# 7-PWM_INTERLOCK.net
KiCad netlist of a schematic drawn in Altium Designer
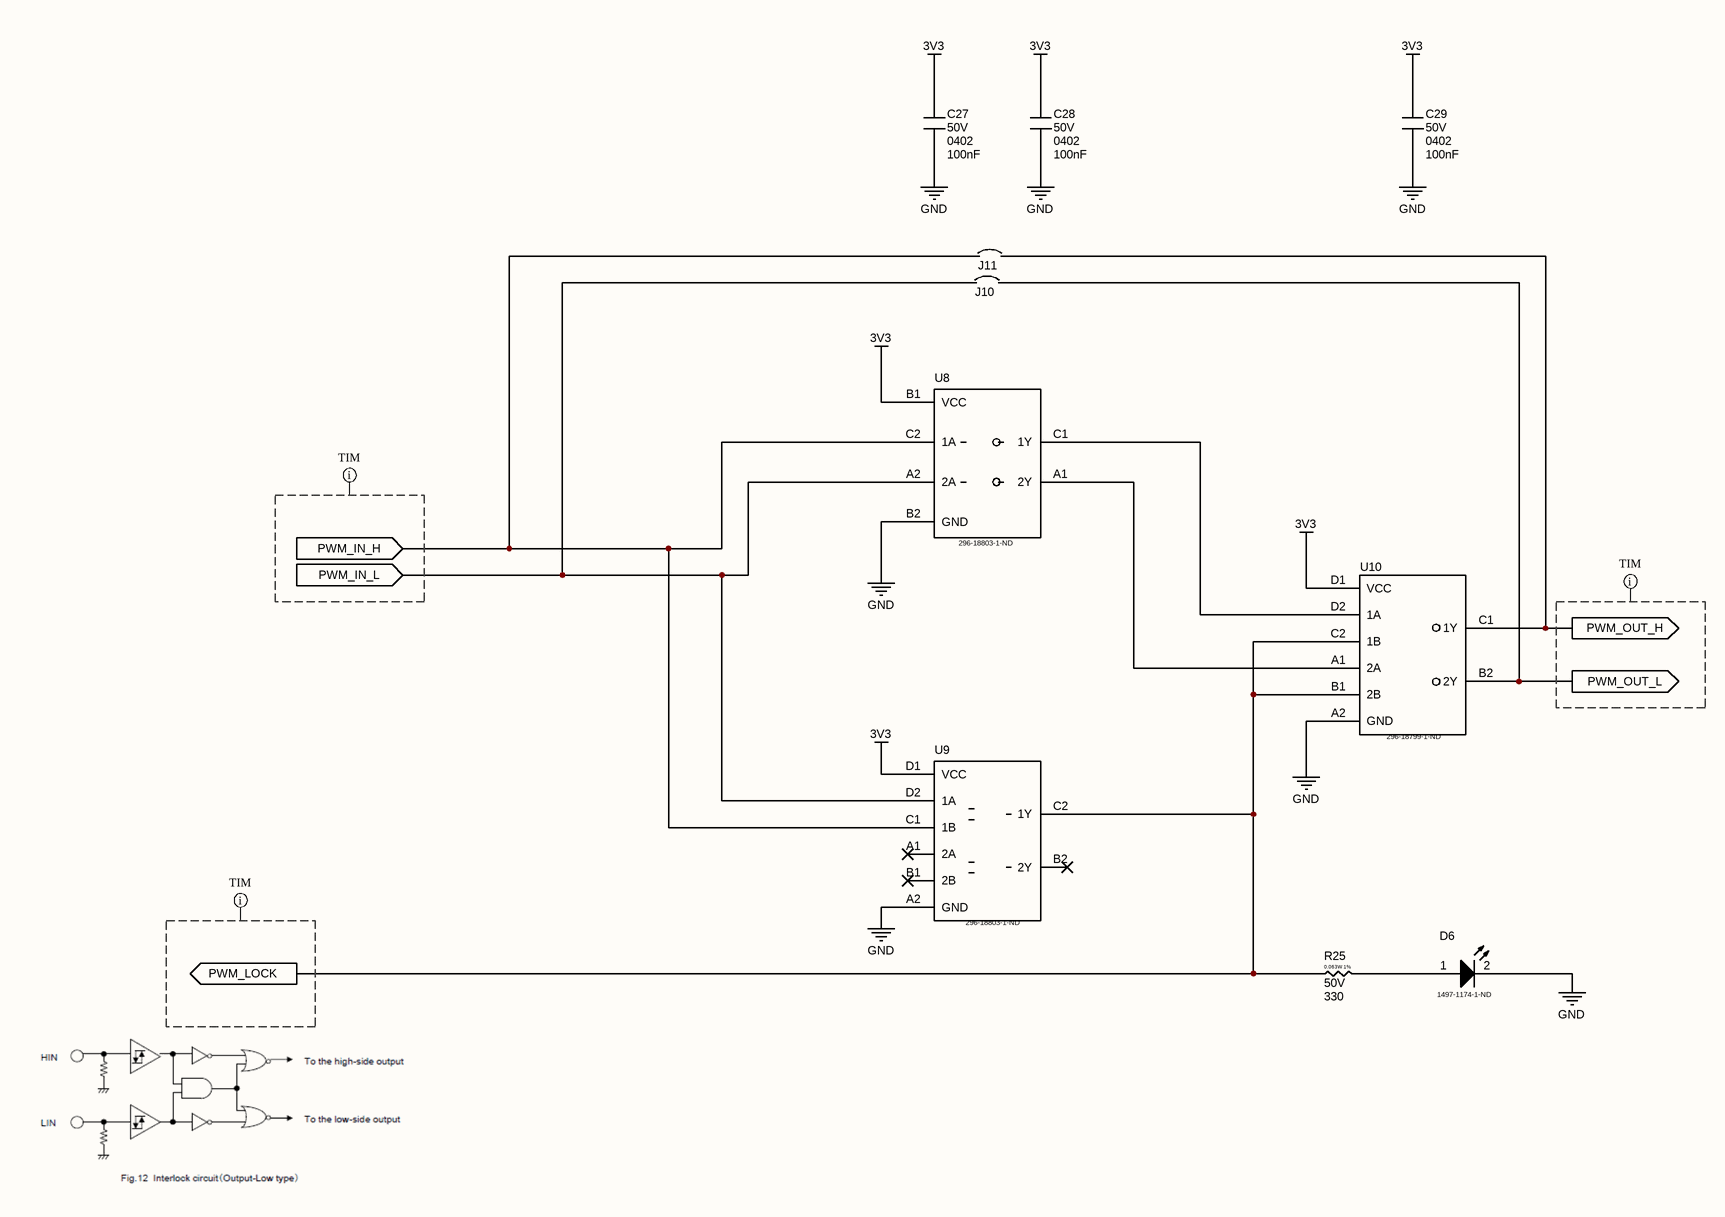
[diagram p0: 7-PWM_INTERLOCK.SchDoc]

(export (version "E")
  (design (tool "Eeschema 10.0.6"))
  (components
    (comp (ref "C27")
      (value "100nF")
      (footprint "C 0402(1005)x0.5")
      (description "SMD-0402 100nF 50V X7R 10%")
      (fields
        (field (name "PART NUMBER") "CL05B104KB5NNNC")
        (field (name "MANUFACTURER") "Samsung")
        (field (name "VDC") "50V")
        (field (name "PACKAGE") "0402")
        (field (name "PUBLISHER") "Hefest")
      )
      (libsource (lib "LIB_PASSIVE") (part "CAP 0402 100nF 50V X7R"))
    )
    (comp (ref "C28")
      (value "100nF")
      (footprint "C 0402(1005)x0.5")
      (description "SMD-0402 100nF 50V X7R 10%")
      (fields
        (field (name "PART NUMBER") "CL05B104KB5NNNC")
        (field (name "MANUFACTURER") "Samsung")
        (field (name "VDC") "50V")
        (field (name "PACKAGE") "0402")
        (field (name "PUBLISHER") "Hefest")
      )
      (libsource (lib "LIB_PASSIVE") (part "CAP 0402 100nF 50V X7R"))
    )
    (comp (ref "C29")
      (value "100nF")
      (footprint "C 0402(1005)x0.5")
      (description "SMD-0402 100nF 50V X7R 10%")
      (fields
        (field (name "PART NUMBER") "CL05B104KB5NNNC")
        (field (name "MANUFACTURER") "Samsung")
        (field (name "VDC") "50V")
        (field (name "PACKAGE") "0402")
        (field (name "PUBLISHER") "Hefest")
      )
      (libsource (lib "LIB_PASSIVE") (part "CAP 0402 100nF 50V X7R"))
    )
    (comp (ref "D6")
      (value "0402")
      (footprint "LED 0402")
      (description "LED SMD 0402")
      (fields (field (name "SUPPLIER PART NUMBER 1") "1497-1174-1-ND"))
      (libsource (lib "LIB_PASSIVE") (part "LED 0402"))
    )
    (comp (ref "J10")
      (value "SHORT_PARALLEL")
      (footprint "SHORT_PARALLEL")
      (description "SHORTABLE PARALLEL PCB LINK")
      (libsource (lib "LIB_ELECTRO-MECHA") (part "SHORT_PARALLEL"))
    )
    (comp (ref "J11")
      (value "SHORT_PARALLEL")
      (footprint "SHORT_PARALLEL")
      (description "SHORTABLE PARALLEL PCB LINK")
      (libsource (lib "LIB_ELECTRO-MECHA") (part "SHORT_PARALLEL"))
    )
    (comp (ref "R25")
      (value "330")
      (footprint "R 0402(1005)-1%")
      (description "SMD 0402 0.063W 1% 50V")
      (fields
        (field (name "MANUFACTURER") "YAGEO")
        (field (name "POWER") "0.0625W")
        (field (name "VDC") "50V")
        (field (name "PUBLISHER") "Hefest")
      )
      (libsource (lib "LIB_PASSIVE") (part "RES 0402-1%"))
    )
    (comp (ref "U8")
      (value "DSGBA6")
      (footprint "DSBGA-6")
      (description "INV DUAL SCHMITT")
      (fields (field (name "SUPPLIER PART NUMBER 1") "296-18803-1-ND"))
      (libsource (lib "LIB_IC") (part "SN74LVC2G14_BGA"))
    )
    (comp (ref "U9")
      (value "DSGBA8")
      (footprint "DSBGA-8")
      (description "AND DUAL SCHMITT")
      (fields (field (name "SUPPLIER PART NUMBER 1") "296-18803-1-ND"))
      (libsource (lib "LIB_IC") (part "SN74LVC2G08_BGA"))
    )
    (comp (ref "U10")
      (value "DSBGA8")
      (footprint "DSBGA-8")
      (description "NOR DUAL")
      (fields (field (name "SUPPLIER PART NUMBER 1") "296-18799-1-ND"))
      (libsource (lib "LIB_IC") (part "SN74LVC2G02_BGA"))
    )
  )
  (nets
    (net (code "1") (name "/PWM_IN_H") (class "Default")
      (node (ref "J11") (pin "1") (pinfunction "1_1") (pintype "passive"))
      (node (ref "U8") (pin "C2") (pinfunction "1A_C2") (pintype "passive"))
      (node (ref "U9") (pin "C1") (pinfunction "1B_C1") (pintype "passive"))
    )
    (net (code "2") (name "/PWM_IN_L") (class "Default")
      (node (ref "J10") (pin "1") (pinfunction "1_1") (pintype "passive"))
      (node (ref "U8") (pin "A2") (pinfunction "2A_A2") (pintype "passive"))
      (node (ref "U9") (pin "D2") (pinfunction "1A_D2") (pintype "passive"))
    )
    (net (code "3") (name "/PWM_LOCK") (class "Default")
      (node (ref "R25") (pin "1") (pinfunction "1_1") (pintype "passive"))
      (node (ref "U10") (pin "B1") (pinfunction "2B_B1") (pintype "passive"))
      (node (ref "U10") (pin "C2") (pinfunction "1B_C2") (pintype "passive"))
      (node (ref "U9") (pin "C2") (pinfunction "1Y_C2") (pintype "passive"))
    )
    (net (code "4") (name "/PWM_OUT_H") (class "Default")
      (node (ref "J11") (pin "2") (pinfunction "2_2") (pintype "passive"))
      (node (ref "U10") (pin "C1") (pinfunction "1Y_C1") (pintype "passive"))
    )
    (net (code "5") (name "/PWM_OUT_L") (class "Default")
      (node (ref "J10") (pin "2") (pinfunction "2_2") (pintype "passive"))
      (node (ref "U10") (pin "B2") (pinfunction "2Y_B2") (pintype "passive"))
    )
    (net (code "6") (name "3V3") (class "Default")
      (node (ref "C27") (pin "1") (pinfunction "1_1") (pintype "passive"))
      (node (ref "C28") (pin "1") (pinfunction "1_1") (pintype "passive"))
      (node (ref "C29") (pin "1") (pinfunction "1_1") (pintype "passive"))
      (node (ref "U10") (pin "D1") (pinfunction "VCC_D1") (pintype "passive"))
      (node (ref "U8") (pin "B1") (pinfunction "VCC_B1") (pintype "passive"))
      (node (ref "U9") (pin "D1") (pinfunction "VCC_D1") (pintype "passive"))
    )
    (net (code "7") (name "GND") (class "Default")
      (node (ref "C27") (pin "2") (pinfunction "2_2") (pintype "passive"))
      (node (ref "C28") (pin "2") (pinfunction "2_2") (pintype "passive"))
      (node (ref "C29") (pin "2") (pinfunction "2_2") (pintype "passive"))
      (node (ref "D6") (pin "2") (pinfunction "2_2") (pintype "passive"))
      (node (ref "U10") (pin "A2") (pinfunction "GND_A2") (pintype "passive"))
      (node (ref "U8") (pin "B2") (pinfunction "GND_B2") (pintype "passive"))
      (node (ref "U9") (pin "A2") (pinfunction "GND_A2") (pintype "passive"))
    )
    (net (code "8") (name "Net-(D6-Pad1)") (class "Default")
      (node (ref "D6") (pin "1") (pinfunction "1_1") (pintype "passive"))
      (node (ref "R25") (pin "2") (pinfunction "2_2") (pintype "passive"))
    )
    (net (code "9") (name "Net-(U10-1A)") (class "Default")
      (node (ref "U10") (pin "D2") (pinfunction "1A_D2") (pintype "passive"))
      (node (ref "U8") (pin "C1") (pinfunction "1Y_C1") (pintype "passive"))
    )
    (net (code "10") (name "Net-(U10-2A)") (class "Default")
      (node (ref "U10") (pin "A1") (pinfunction "2A_A1") (pintype "passive"))
      (node (ref "U8") (pin "A1") (pinfunction "2Y_A1") (pintype "passive"))
    )
    (net (code "11") (name "unconnected-(U9-2A-PadA1)") (class "Default")
      (node (ref "U9") (pin "A1") (pinfunction "2A_A1") (pintype "passive+no_connect"))
    )
    (net (code "12") (name "unconnected-(U9-2B-PadB1)") (class "Default")
      (node (ref "U9") (pin "B1") (pinfunction "2B_B1") (pintype "passive+no_connect"))
    )
    (net (code "13") (name "unconnected-(U9-2Y-PadB2)") (class "Default")
      (node (ref "U9") (pin "B2") (pinfunction "2Y_B2") (pintype "passive+no_connect"))
    )
  )
)
